# i2cping_hw1_0.net
KiCad netlist of a schematic drawn in EAGLE
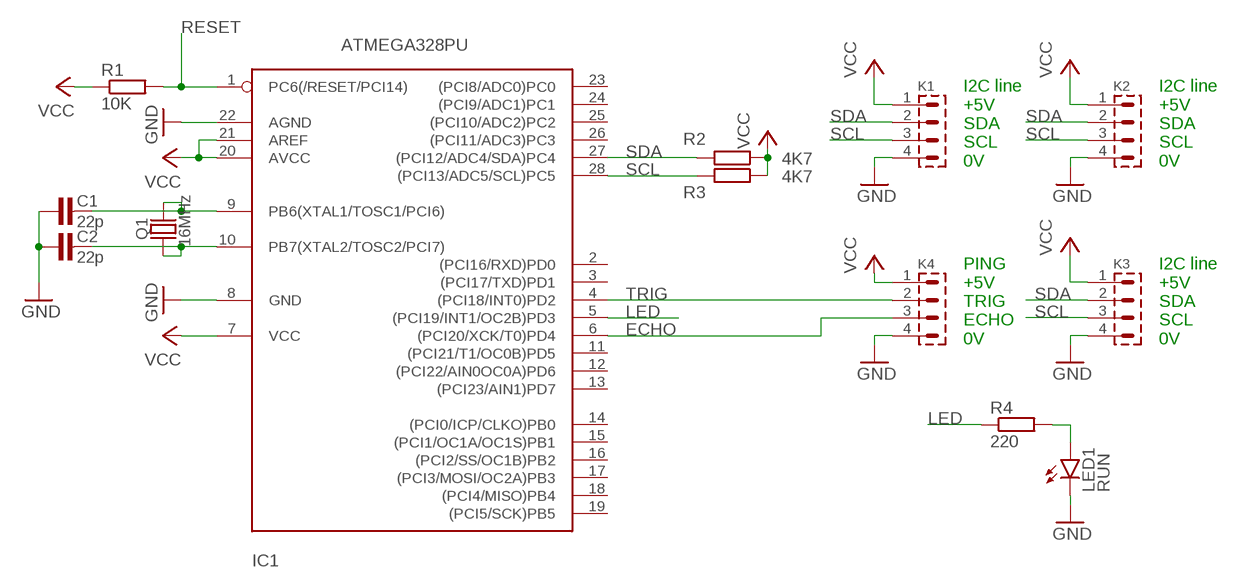
[diagram p0: schematic, sheet 1]

(export (version "E")
  (design (tool "Eeschema 10.0.6"))
  (components
    (comp (ref "C1")
      (value "22p")
      (footprint "eagle-import:C-5")
      (libsource (lib "eagle-import") (part "C-KER_5"))
    )
    (comp (ref "C2")
      (value "22p")
      (footprint "eagle-import:C-5")
      (libsource (lib "eagle-import") (part "C-KER_5"))
    )
    (comp (ref "IC1")
      (value "ATMEGA328PU")
      (footprint "eagle-import:DIL28-3")
      (libsource (lib "eagle-import") (part "ATMEGA168P-20"))
    )
    (comp (ref "K1")
      (value "PSH02-04P")
      (footprint "eagle-import:PSH02-04P")
      (libsource (lib "eagle-import") (part "PSH02-04P"))
    )
    (comp (ref "K2")
      (value "PSH02-04P")
      (footprint "eagle-import:PSH02-04P")
      (libsource (lib "eagle-import") (part "PSH02-04P"))
    )
    (comp (ref "K3")
      (value "PSH02-04P")
      (footprint "eagle-import:PSH02-04P")
      (libsource (lib "eagle-import") (part "PSH02-04P"))
    )
    (comp (ref "K4")
      (value "PSH02-04P")
      (footprint "eagle-import:PSH02-04P")
      (libsource (lib "eagle-import") (part "PSH02-04P"))
    )
    (comp (ref "LED1")
      (value "RUN")
      (footprint "eagle-import:LED5MM")
      (libsource (lib "eagle-import") (part "LED5MM"))
    )
    (comp (ref "Q1")
      (value "16MHz")
      (footprint "eagle-import:HC-49U")
      (libsource (lib "eagle-import") (part "Q_HC-49U"))
    )
    (comp (ref "R1")
      (value "10K")
      (footprint "eagle-import:0207_7")
      (libsource (lib "eagle-import") (part "R-EU_0207/7"))
    )
    (comp (ref "R2")
      (value "4K7")
      (footprint "eagle-import:0207_7")
      (libsource (lib "eagle-import") (part "R-EU_0207/7"))
    )
    (comp (ref "R3")
      (value "4K7")
      (footprint "eagle-import:0207_7")
      (libsource (lib "eagle-import") (part "R-EU_0207/7"))
    )
    (comp (ref "R4")
      (value "220")
      (footprint "eagle-import:0207_7")
      (libsource (lib "eagle-import") (part "R-EU_0207/7"))
    )
  )
  (nets
    (net (code "1") (name "/ECHO") (class "Default")
      (node (ref "IC1") (pin "6") (pinfunction "(PCI20/XCK/T0)PD4_6") (pintype "bidirectional"))
      (node (ref "K4") (pin "3") (pinfunction "3_3") (pintype "passive"))
    )
    (net (code "2") (name "/LED") (class "Default")
      (node (ref "IC1") (pin "5") (pinfunction "(PCI19/INT1/OC2B)PD3_5") (pintype "bidirectional"))
      (node (ref "R4") (pin "1") (pinfunction "1_1") (pintype "passive"))
    )
    (net (code "3") (name "/RESET") (class "Default")
      (node (ref "IC1") (pin "1") (pinfunction "PC6(/RESET/PCI14)_1") (pintype "bidirectional"))
      (node (ref "R1") (pin "2") (pinfunction "2_2") (pintype "passive"))
    )
    (net (code "4") (name "/SCL") (class "Default")
      (node (ref "IC1") (pin "28") (pinfunction "(PCI13/ADC5/SCL)PC5_28") (pintype "bidirectional"))
      (node (ref "K1") (pin "3") (pinfunction "3_3") (pintype "passive"))
      (node (ref "K2") (pin "3") (pinfunction "3_3") (pintype "passive"))
      (node (ref "K3") (pin "3") (pinfunction "3_3") (pintype "passive"))
      (node (ref "R3") (pin "2") (pinfunction "2_2") (pintype "passive"))
    )
    (net (code "5") (name "/SDA") (class "Default")
      (node (ref "IC1") (pin "27") (pinfunction "(PCI12/ADC4/SDA)PC4_27") (pintype "bidirectional"))
      (node (ref "K1") (pin "2") (pinfunction "2_2") (pintype "passive"))
      (node (ref "K2") (pin "2") (pinfunction "2_2") (pintype "passive"))
      (node (ref "K3") (pin "2") (pinfunction "2_2") (pintype "passive"))
      (node (ref "R2") (pin "2") (pinfunction "2_2") (pintype "passive"))
    )
    (net (code "6") (name "/TRIG") (class "Default")
      (node (ref "IC1") (pin "4") (pinfunction "(PCI18/INT0)PD2_4") (pintype "bidirectional"))
      (node (ref "K4") (pin "2") (pinfunction "2_2") (pintype "passive"))
    )
    (net (code "7") (name "GND") (class "Default")
      (node (ref "C1") (pin "1") (pinfunction "1_1") (pintype "passive"))
      (node (ref "C2") (pin "1") (pinfunction "1_1") (pintype "passive"))
      (node (ref "IC1") (pin "22") (pinfunction "AGND_22") (pintype "bidirectional"))
      (node (ref "IC1") (pin "8") (pinfunction "GND_8") (pintype "bidirectional"))
      (node (ref "K1") (pin "4") (pinfunction "4_4") (pintype "passive"))
      (node (ref "K2") (pin "4") (pinfunction "4_4") (pintype "passive"))
      (node (ref "K3") (pin "4") (pinfunction "4_4") (pintype "passive"))
      (node (ref "K4") (pin "4") (pinfunction "4_4") (pintype "passive"))
      (node (ref "LED1") (pin "K") (pinfunction "C_K") (pintype "passive"))
    )
    (net (code "8") (name "Net-(IC1-PB6(XTAL1{slash}TOSC1{slash}PCI6))") (class "Default")
      (node (ref "C1") (pin "2") (pinfunction "2_2") (pintype "passive"))
      (node (ref "IC1") (pin "9") (pinfunction "PB6(XTAL1/TOSC1/PCI6)_9") (pintype "bidirectional"))
      (node (ref "Q1") (pin "2") (pinfunction "2_2") (pintype "passive"))
    )
    (net (code "9") (name "Net-(IC1-PB7(XTAL2{slash}TOSC2{slash}PCI7))") (class "Default")
      (node (ref "C2") (pin "2") (pinfunction "2_2") (pintype "passive"))
      (node (ref "IC1") (pin "10") (pinfunction "PB7(XTAL2/TOSC2/PCI7)_10") (pintype "bidirectional"))
      (node (ref "Q1") (pin "1") (pinfunction "1_1") (pintype "passive"))
    )
    (net (code "10") (name "Net-(LED1-PadA)") (class "Default")
      (node (ref "LED1") (pin "A") (pinfunction "A_A") (pintype "passive"))
      (node (ref "R4") (pin "2") (pinfunction "2_2") (pintype "passive"))
    )
    (net (code "11") (name "VCC") (class "Default")
      (node (ref "IC1") (pin "20") (pinfunction "AVCC_20") (pintype "bidirectional"))
      (node (ref "IC1") (pin "21") (pinfunction "AREF_21") (pintype "bidirectional"))
      (node (ref "IC1") (pin "7") (pinfunction "VCC_7") (pintype "bidirectional"))
      (node (ref "K1") (pin "1") (pinfunction "1_1") (pintype "passive"))
      (node (ref "K2") (pin "1") (pinfunction "1_1") (pintype "passive"))
      (node (ref "K3") (pin "1") (pinfunction "1_1") (pintype "passive"))
      (node (ref "K4") (pin "1") (pinfunction "1_1") (pintype "passive"))
      (node (ref "R1") (pin "1") (pinfunction "1_1") (pintype "passive"))
      (node (ref "R2") (pin "1") (pinfunction "1_1") (pintype "passive"))
      (node (ref "R3") (pin "1") (pinfunction "1_1") (pintype "passive"))
    )
    (net (code "12") (name "unconnected-(IC1-(PCI0{slash}ICP{slash}CLKO)PB0-Pad14)") (class "Default")
      (node (ref "IC1") (pin "14") (pinfunction "(PCI0/ICP/CLKO)PB0_14") (pintype "bidirectional"))
    )
    (net (code "13") (name "unconnected-(IC1-(PCI1{slash}OC1A{slash}OC1S)PB1-Pad15)") (class "Default")
      (node (ref "IC1") (pin "15") (pinfunction "(PCI1/OC1A/OC1S)PB1_15") (pintype "bidirectional"))
    )
    (net (code "14") (name "unconnected-(IC1-(PCI2{slash}SS{slash}OC1B)PB2-Pad16)") (class "Default")
      (node (ref "IC1") (pin "16") (pinfunction "(PCI2/SS/OC1B)PB2_16") (pintype "bidirectional"))
    )
    (net (code "15") (name "unconnected-(IC1-(PCI3{slash}MOSI{slash}OC2A)PB3-Pad17)") (class "Default")
      (node (ref "IC1") (pin "17") (pinfunction "(PCI3/MOSI/OC2A)PB3_17") (pintype "bidirectional"))
    )
    (net (code "16") (name "unconnected-(IC1-(PCI4{slash}MISO)PB4-Pad18)") (class "Default")
      (node (ref "IC1") (pin "18") (pinfunction "(PCI4/MISO)PB4_18") (pintype "bidirectional"))
    )
    (net (code "17") (name "unconnected-(IC1-(PCI5{slash}SCK)PB5-Pad19)") (class "Default")
      (node (ref "IC1") (pin "19") (pinfunction "(PCI5/SCK)PB5_19") (pintype "bidirectional"))
    )
    (net (code "18") (name "unconnected-(IC1-(PCI8{slash}ADC0)PC0-Pad23)") (class "Default")
      (node (ref "IC1") (pin "23") (pinfunction "(PCI8/ADC0)PC0_23") (pintype "bidirectional"))
    )
    (net (code "19") (name "unconnected-(IC1-(PCI9{slash}ADC1)PC1-Pad24)") (class "Default")
      (node (ref "IC1") (pin "24") (pinfunction "(PCI9/ADC1)PC1_24") (pintype "bidirectional"))
    )
    (net (code "20") (name "unconnected-(IC1-(PCI10{slash}ADC2)PC2-Pad25)") (class "Default")
      (node (ref "IC1") (pin "25") (pinfunction "(PCI10/ADC2)PC2_25") (pintype "bidirectional"))
    )
    (net (code "21") (name "unconnected-(IC1-(PCI11{slash}ADC3)PC3-Pad26)") (class "Default")
      (node (ref "IC1") (pin "26") (pinfunction "(PCI11/ADC3)PC3_26") (pintype "bidirectional"))
    )
    (net (code "22") (name "unconnected-(IC1-(PCI16{slash}RXD)PD0-Pad2)") (class "Default")
      (node (ref "IC1") (pin "2") (pinfunction "(PCI16/RXD)PD0_2") (pintype "bidirectional"))
    )
    (net (code "23") (name "unconnected-(IC1-(PCI17{slash}TXD)PD1-Pad3)") (class "Default")
      (node (ref "IC1") (pin "3") (pinfunction "(PCI17/TXD)PD1_3") (pintype "bidirectional"))
    )
    (net (code "24") (name "unconnected-(IC1-(PCI21{slash}T1{slash}OC0B)PD5-Pad11)") (class "Default")
      (node (ref "IC1") (pin "11") (pinfunction "(PCI21/T1/OC0B)PD5_11") (pintype "bidirectional"))
    )
    (net (code "25") (name "unconnected-(IC1-(PCI22{slash}AIN0OC0A)PD6-Pad12)") (class "Default")
      (node (ref "IC1") (pin "12") (pinfunction "(PCI22/AIN0OC0A)PD6_12") (pintype "bidirectional"))
    )
    (net (code "26") (name "unconnected-(IC1-(PCI23{slash}AIN1)PD7-Pad13)") (class "Default")
      (node (ref "IC1") (pin "13") (pinfunction "(PCI23/AIN1)PD7_13") (pintype "bidirectional"))
    )
  )
)
